# SimpleTimerPCB.net
KiCad netlist of a schematic drawn in EAGLE
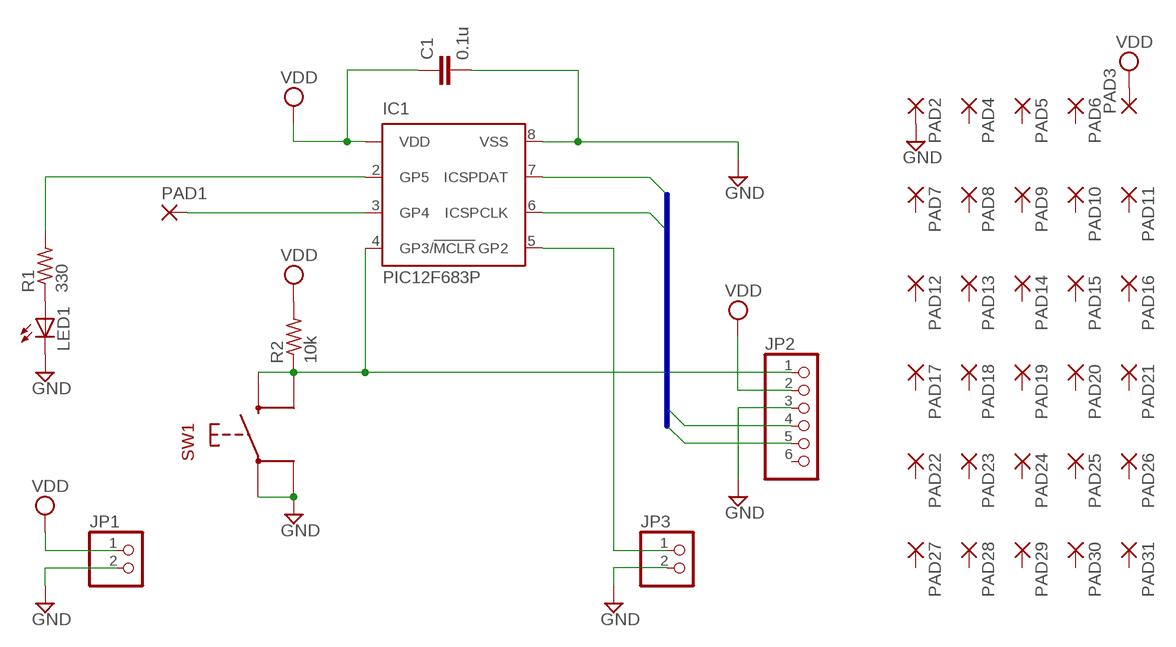
[diagram p0: schematic, sheet 1]

(export (version "E")
  (design (tool "Eeschema 10.0.6"))
  (components
    (comp (ref "C1")
      (value "0.1u")
      (footprint "eagle-import:C050-024X044")
      (libsource (lib "eagle-import") (part "C-EU050-024X044"))
    )
    (comp (ref "IC1")
      (value "PIC12F683P")
      (footprint "eagle-import:DIL8")
      (fields (field (name "MF") "MICROCHIP") (field (name "MPN") "PIC12F683-I/P"))
      (libsource (lib "eagle-import") (part "PIC12F683P"))
    )
    (comp (ref "JP1")
      (value "PINHD-1X2")
      (footprint "eagle-import:1X02")
      (libsource (lib "eagle-import") (part "PINHD-1X2"))
    )
    (comp (ref "JP2")
      (value "PINHD-1X6")
      (footprint "eagle-import:1X06")
      (libsource (lib "eagle-import") (part "PINHD-1X6"))
    )
    (comp (ref "JP3")
      (value "PINHD-1X2")
      (footprint "eagle-import:1X02")
      (libsource (lib "eagle-import") (part "PINHD-1X2"))
    )
    (comp (ref "LED1")
      (value "LED3MM")
      (footprint "eagle-import:LED3MM")
      (libsource (lib "eagle-import") (part "LED3MM"))
    )
    (comp (ref "PAD1")
      (value "1,6/0,9")
      (footprint "eagle-import:1,6_0,9")
      (libsource (lib "eagle-import") (part "1,6/0,9"))
    )
    (comp (ref "PAD2")
      (value "1,6/0,9")
      (footprint "eagle-import:1,6_0,9")
      (libsource (lib "eagle-import") (part "1,6/0,9"))
    )
    (comp (ref "PAD3")
      (value "1,6/0,9")
      (footprint "eagle-import:1,6_0,9")
      (libsource (lib "eagle-import") (part "1,6/0,9"))
    )
    (comp (ref "PAD4")
      (value "1,6/0,9")
      (footprint "eagle-import:1,6_0,9")
      (libsource (lib "eagle-import") (part "1,6/0,9"))
    )
    (comp (ref "PAD5")
      (value "1,6/0,9")
      (footprint "eagle-import:1,6_0,9")
      (libsource (lib "eagle-import") (part "1,6/0,9"))
    )
    (comp (ref "PAD6")
      (value "1,6/0,9")
      (footprint "eagle-import:1,6_0,9")
      (libsource (lib "eagle-import") (part "1,6/0,9"))
    )
    (comp (ref "PAD7")
      (value "1,6/0,9")
      (footprint "eagle-import:1,6_0,9")
      (libsource (lib "eagle-import") (part "1,6/0,9"))
    )
    (comp (ref "PAD8")
      (value "1,6/0,9")
      (footprint "eagle-import:1,6_0,9")
      (libsource (lib "eagle-import") (part "1,6/0,9"))
    )
    (comp (ref "PAD9")
      (value "1,6/0,9")
      (footprint "eagle-import:1,6_0,9")
      (libsource (lib "eagle-import") (part "1,6/0,9"))
    )
    (comp (ref "PAD10")
      (value "1,6/0,9")
      (footprint "eagle-import:1,6_0,9")
      (libsource (lib "eagle-import") (part "1,6/0,9"))
    )
    (comp (ref "PAD11")
      (value "1,6/0,9")
      (footprint "eagle-import:1,6_0,9")
      (libsource (lib "eagle-import") (part "1,6/0,9"))
    )
    (comp (ref "PAD12")
      (value "1,6/0,9")
      (footprint "eagle-import:1,6_0,9")
      (libsource (lib "eagle-import") (part "1,6/0,9"))
    )
    (comp (ref "PAD13")
      (value "1,6/0,9")
      (footprint "eagle-import:1,6_0,9")
      (libsource (lib "eagle-import") (part "1,6/0,9"))
    )
    (comp (ref "PAD14")
      (value "1,6/0,9")
      (footprint "eagle-import:1,6_0,9")
      (libsource (lib "eagle-import") (part "1,6/0,9"))
    )
    (comp (ref "PAD15")
      (value "1,6/0,9")
      (footprint "eagle-import:1,6_0,9")
      (libsource (lib "eagle-import") (part "1,6/0,9"))
    )
    (comp (ref "PAD16")
      (value "1,6/0,9")
      (footprint "eagle-import:1,6_0,9")
      (libsource (lib "eagle-import") (part "1,6/0,9"))
    )
    (comp (ref "PAD17")
      (value "1,6/0,9")
      (footprint "eagle-import:1,6_0,9")
      (libsource (lib "eagle-import") (part "1,6/0,9"))
    )
    (comp (ref "PAD18")
      (value "1,6/0,9")
      (footprint "eagle-import:1,6_0,9")
      (libsource (lib "eagle-import") (part "1,6/0,9"))
    )
    (comp (ref "PAD19")
      (value "1,6/0,9")
      (footprint "eagle-import:1,6_0,9")
      (libsource (lib "eagle-import") (part "1,6/0,9"))
    )
    (comp (ref "PAD20")
      (value "1,6/0,9")
      (footprint "eagle-import:1,6_0,9")
      (libsource (lib "eagle-import") (part "1,6/0,9"))
    )
    (comp (ref "PAD21")
      (value "1,6/0,9")
      (footprint "eagle-import:1,6_0,9")
      (libsource (lib "eagle-import") (part "1,6/0,9"))
    )
    (comp (ref "PAD22")
      (value "1,6/0,9")
      (footprint "eagle-import:1,6_0,9")
      (libsource (lib "eagle-import") (part "1,6/0,9"))
    )
    (comp (ref "PAD23")
      (value "1,6/0,9")
      (footprint "eagle-import:1,6_0,9")
      (libsource (lib "eagle-import") (part "1,6/0,9"))
    )
    (comp (ref "PAD24")
      (value "1,6/0,9")
      (footprint "eagle-import:1,6_0,9")
      (libsource (lib "eagle-import") (part "1,6/0,9"))
    )
    (comp (ref "PAD25")
      (value "1,6/0,9")
      (footprint "eagle-import:1,6_0,9")
      (libsource (lib "eagle-import") (part "1,6/0,9"))
    )
    (comp (ref "PAD26")
      (value "1,6/0,9")
      (footprint "eagle-import:1,6_0,9")
      (libsource (lib "eagle-import") (part "1,6/0,9"))
    )
    (comp (ref "PAD27")
      (value "1,6/0,9")
      (footprint "eagle-import:1,6_0,9")
      (libsource (lib "eagle-import") (part "1,6/0,9"))
    )
    (comp (ref "PAD28")
      (value "1,6/0,9")
      (footprint "eagle-import:1,6_0,9")
      (libsource (lib "eagle-import") (part "1,6/0,9"))
    )
    (comp (ref "PAD29")
      (value "1,6/0,9")
      (footprint "eagle-import:1,6_0,9")
      (libsource (lib "eagle-import") (part "1,6/0,9"))
    )
    (comp (ref "PAD30")
      (value "1,6/0,9")
      (footprint "eagle-import:1,6_0,9")
      (libsource (lib "eagle-import") (part "1,6/0,9"))
    )
    (comp (ref "PAD31")
      (value "1,6/0,9")
      (footprint "eagle-import:1,6_0,9")
      (libsource (lib "eagle-import") (part "1,6/0,9"))
    )
    (comp (ref "R1")
      (value "330")
      (footprint "eagle-import:0204_7")
      (libsource (lib "eagle-import") (part "R-US_0204/7"))
    )
    (comp (ref "R2")
      (value "10k")
      (footprint "eagle-import:0204_7")
      (libsource (lib "eagle-import") (part "R-US_0204/7"))
    )
    (comp (ref "SW1")
      (value "TACT-SWITCH")
      (footprint "eagle-import:TACTSW-25X20")
      (libsource (lib "eagle-import") (part "TACT-SWITCH"))
    )
  )
  (nets
    (net (code "1") (name "/PIN4") (class "Default")
      (node (ref "IC1") (pin "7") (pinfunction "ICSPDAT_7") (pintype "bidirectional"))
      (node (ref "JP2") (pin "4") (pinfunction "4_4") (pintype "passive"))
    )
    (net (code "2") (name "/PIN5") (class "Default")
      (node (ref "IC1") (pin "6") (pinfunction "ICSPCLK_6") (pintype "bidirectional"))
      (node (ref "JP2") (pin "5") (pinfunction "5_5") (pintype "passive"))
    )
    (net (code "3") (name "GND") (class "Default")
      (node (ref "C1") (pin "2") (pinfunction "2_2") (pintype "passive"))
      (node (ref "IC1") (pin "8") (pinfunction "VSS_8") (pintype "power_in"))
      (node (ref "JP1") (pin "2") (pinfunction "2_2") (pintype "passive"))
      (node (ref "JP2") (pin "3") (pinfunction "3_3") (pintype "passive"))
      (node (ref "JP3") (pin "2") (pinfunction "2_2") (pintype "passive"))
      (node (ref "LED1") (pin "K") (pinfunction "C_K") (pintype "passive"))
      (node (ref "PAD2") (pin "1") (pinfunction "P_1") (pintype "passive"))
      (node (ref "SW1") (pin "3") (pinfunction "P1_3") (pintype "passive"))
      (node (ref "SW1") (pin "4") (pinfunction "P2_4") (pintype "passive"))
    )
    (net (code "4") (name "Net-(IC1-GP2)") (class "Default")
      (node (ref "IC1") (pin "5") (pinfunction "GP2_5") (pintype "bidirectional"))
      (node (ref "JP3") (pin "1") (pinfunction "1_1") (pintype "passive"))
    )
    (net (code "5") (name "Net-(IC1-GP3{slash}~{MCLR})") (class "Default")
      (node (ref "IC1") (pin "4") (pinfunction "GP3/~{MCLR}_4") (pintype "bidirectional"))
      (node (ref "JP2") (pin "1") (pinfunction "1_1") (pintype "passive"))
      (node (ref "R2") (pin "1") (pinfunction "1_1") (pintype "passive"))
      (node (ref "SW1") (pin "1") (pinfunction "S1_1") (pintype "passive"))
      (node (ref "SW1") (pin "2") (pinfunction "S2_2") (pintype "passive"))
    )
    (net (code "6") (name "Net-(IC1-GP4)") (class "Default")
      (node (ref "IC1") (pin "3") (pinfunction "GP4_3") (pintype "bidirectional"))
      (node (ref "PAD1") (pin "1") (pinfunction "P_1") (pintype "passive"))
    )
    (net (code "7") (name "Net-(IC1-GP5)") (class "Default")
      (node (ref "IC1") (pin "2") (pinfunction "GP5_2") (pintype "bidirectional"))
      (node (ref "R1") (pin "2") (pinfunction "2_2") (pintype "passive"))
    )
    (net (code "8") (name "Net-(LED1-PadA)") (class "Default")
      (node (ref "LED1") (pin "A") (pinfunction "A_A") (pintype "passive"))
      (node (ref "R1") (pin "1") (pinfunction "1_1") (pintype "passive"))
    )
    (net (code "9") (name "VDD") (class "Default")
      (node (ref "C1") (pin "1") (pinfunction "1_1") (pintype "passive"))
      (node (ref "IC1") (pin "1") (pinfunction "VDD_1") (pintype "power_in"))
      (node (ref "JP1") (pin "1") (pinfunction "1_1") (pintype "passive"))
      (node (ref "JP2") (pin "2") (pinfunction "2_2") (pintype "passive"))
      (node (ref "PAD3") (pin "1") (pinfunction "P_1") (pintype "passive"))
      (node (ref "R2") (pin "2") (pinfunction "2_2") (pintype "passive"))
    )
    (net (code "10") (name "unconnected-(JP2-Pad6)") (class "Default")
      (node (ref "JP2") (pin "6") (pinfunction "6_6") (pintype "passive"))
    )
    (net (code "11") (name "unconnected-(PAD4-P-Pad1)") (class "Default")
      (node (ref "PAD4") (pin "1") (pinfunction "P_1") (pintype "passive"))
    )
    (net (code "12") (name "unconnected-(PAD5-P-Pad1)") (class "Default")
      (node (ref "PAD5") (pin "1") (pinfunction "P_1") (pintype "passive"))
    )
    (net (code "13") (name "unconnected-(PAD6-P-Pad1)") (class "Default")
      (node (ref "PAD6") (pin "1") (pinfunction "P_1") (pintype "passive"))
    )
    (net (code "14") (name "unconnected-(PAD7-P-Pad1)") (class "Default")
      (node (ref "PAD7") (pin "1") (pinfunction "P_1") (pintype "passive"))
    )
    (net (code "15") (name "unconnected-(PAD8-P-Pad1)") (class "Default")
      (node (ref "PAD8") (pin "1") (pinfunction "P_1") (pintype "passive"))
    )
    (net (code "16") (name "unconnected-(PAD9-P-Pad1)") (class "Default")
      (node (ref "PAD9") (pin "1") (pinfunction "P_1") (pintype "passive"))
    )
    (net (code "17") (name "unconnected-(PAD10-P-Pad1)") (class "Default")
      (node (ref "PAD10") (pin "1") (pinfunction "P_1") (pintype "passive"))
    )
    (net (code "18") (name "unconnected-(PAD11-P-Pad1)") (class "Default")
      (node (ref "PAD11") (pin "1") (pinfunction "P_1") (pintype "passive"))
    )
    (net (code "19") (name "unconnected-(PAD12-P-Pad1)") (class "Default")
      (node (ref "PAD12") (pin "1") (pinfunction "P_1") (pintype "passive"))
    )
    (net (code "20") (name "unconnected-(PAD13-P-Pad1)") (class "Default")
      (node (ref "PAD13") (pin "1") (pinfunction "P_1") (pintype "passive"))
    )
    (net (code "21") (name "unconnected-(PAD14-P-Pad1)") (class "Default")
      (node (ref "PAD14") (pin "1") (pinfunction "P_1") (pintype "passive"))
    )
    (net (code "22") (name "unconnected-(PAD15-P-Pad1)") (class "Default")
      (node (ref "PAD15") (pin "1") (pinfunction "P_1") (pintype "passive"))
    )
    (net (code "23") (name "unconnected-(PAD16-P-Pad1)") (class "Default")
      (node (ref "PAD16") (pin "1") (pinfunction "P_1") (pintype "passive"))
    )
    (net (code "24") (name "unconnected-(PAD17-P-Pad1)") (class "Default")
      (node (ref "PAD17") (pin "1") (pinfunction "P_1") (pintype "passive"))
    )
    (net (code "25") (name "unconnected-(PAD18-P-Pad1)") (class "Default")
      (node (ref "PAD18") (pin "1") (pinfunction "P_1") (pintype "passive"))
    )
    (net (code "26") (name "unconnected-(PAD19-P-Pad1)") (class "Default")
      (node (ref "PAD19") (pin "1") (pinfunction "P_1") (pintype "passive"))
    )
    (net (code "27") (name "unconnected-(PAD20-P-Pad1)") (class "Default")
      (node (ref "PAD20") (pin "1") (pinfunction "P_1") (pintype "passive"))
    )
    (net (code "28") (name "unconnected-(PAD21-P-Pad1)") (class "Default")
      (node (ref "PAD21") (pin "1") (pinfunction "P_1") (pintype "passive"))
    )
    (net (code "29") (name "unconnected-(PAD22-P-Pad1)") (class "Default")
      (node (ref "PAD22") (pin "1") (pinfunction "P_1") (pintype "passive"))
    )
    (net (code "30") (name "unconnected-(PAD23-P-Pad1)") (class "Default")
      (node (ref "PAD23") (pin "1") (pinfunction "P_1") (pintype "passive"))
    )
    (net (code "31") (name "unconnected-(PAD24-P-Pad1)") (class "Default")
      (node (ref "PAD24") (pin "1") (pinfunction "P_1") (pintype "passive"))
    )
    (net (code "32") (name "unconnected-(PAD25-P-Pad1)") (class "Default")
      (node (ref "PAD25") (pin "1") (pinfunction "P_1") (pintype "passive"))
    )
    (net (code "33") (name "unconnected-(PAD26-P-Pad1)") (class "Default")
      (node (ref "PAD26") (pin "1") (pinfunction "P_1") (pintype "passive"))
    )
    (net (code "34") (name "unconnected-(PAD27-P-Pad1)") (class "Default")
      (node (ref "PAD27") (pin "1") (pinfunction "P_1") (pintype "passive"))
    )
    (net (code "35") (name "unconnected-(PAD28-P-Pad1)") (class "Default")
      (node (ref "PAD28") (pin "1") (pinfunction "P_1") (pintype "passive"))
    )
    (net (code "36") (name "unconnected-(PAD29-P-Pad1)") (class "Default")
      (node (ref "PAD29") (pin "1") (pinfunction "P_1") (pintype "passive"))
    )
    (net (code "37") (name "unconnected-(PAD30-P-Pad1)") (class "Default")
      (node (ref "PAD30") (pin "1") (pinfunction "P_1") (pintype "passive"))
    )
    (net (code "38") (name "unconnected-(PAD31-P-Pad1)") (class "Default")
      (node (ref "PAD31") (pin "1") (pinfunction "P_1") (pintype "passive"))
    )
  )
)
